# Tikkenteller.net
KiCad netlist of a schematic drawn in EAGLE
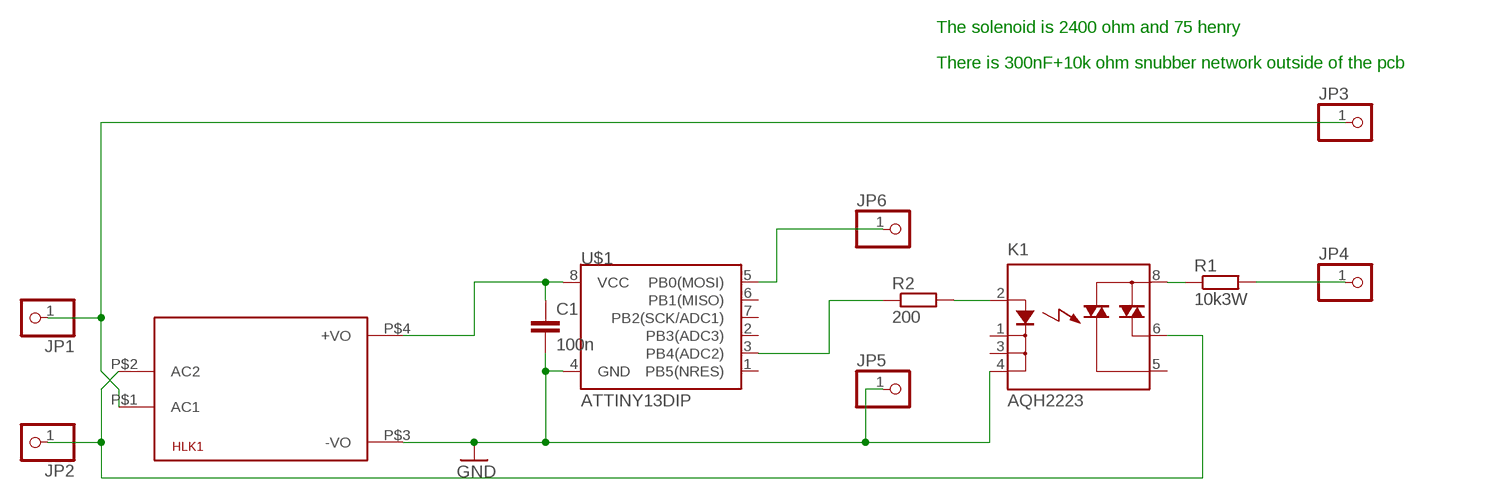
[diagram p0: schematic, sheet 1]

(export (version "E")
  (design (tool "Eeschema 10.0.6"))
  (components
    (comp (ref "C1")
      (value "100n")
      (footprint "eagle-import:C050-024X044")
      (libsource (lib "eagle-import") (part "C-EU050-024X044"))
    )
    (comp (ref "HLK1")
      (value "HLK-PM013W")
      (footprint "eagle-import:HLK-PM01")
      (libsource (lib "eagle-import") (part "HLK-PM013W"))
    )
    (comp (ref "JP1")
      (value "PINHD-1X1")
      (footprint "eagle-import:1X01")
      (libsource (lib "eagle-import") (part "PINHD-1X1"))
    )
    (comp (ref "JP2")
      (value "PINHD-1X1")
      (footprint "eagle-import:1X01")
      (libsource (lib "eagle-import") (part "PINHD-1X1"))
    )
    (comp (ref "JP3")
      (value "PINHD-1X1")
      (footprint "eagle-import:1X01")
      (libsource (lib "eagle-import") (part "PINHD-1X1"))
    )
    (comp (ref "JP4")
      (value "PINHD-1X1")
      (footprint "eagle-import:1X01")
      (libsource (lib "eagle-import") (part "PINHD-1X1"))
    )
    (comp (ref "JP5")
      (value "PINHD-1X1")
      (footprint "eagle-import:1X01")
      (libsource (lib "eagle-import") (part "PINHD-1X1"))
    )
    (comp (ref "JP6")
      (value "PINHD-1X1")
      (footprint "eagle-import:1X01")
      (libsource (lib "eagle-import") (part "PINHD-1X1"))
    )
    (comp (ref "K1")
      (value "AQH2223")
      (footprint "eagle-import:DIL07")
      (fields (field (name "MF") "AROMAT/ MATSUSHITA"))
      (libsource (lib "eagle-import") (part "AQH2232"))
    )
    (comp (ref "R1")
      (value "10k3W")
      (footprint "eagle-import:RESISTOR10")
      (libsource (lib "eagle-import") (part "RR10"))
    )
    (comp (ref "R2")
      (value "200")
      (footprint "eagle-import:RESISTOR4")
      (libsource (lib "eagle-import") (part "RR4"))
    )
    (comp (ref "U$1")
      (value "ATTINY13DIP")
      (footprint "eagle-import:DIP08")
      (libsource (lib "eagle-import") (part "ATTINY13DIP"))
    )
  )
  (nets
    (net (code "1") (name "GND") (class "Default")
      (node (ref "C1") (pin "2") (pinfunction "2_2") (pintype "passive"))
      (node (ref "HLK1") (pin "P$3") (pinfunction "-VO_P$3") (pintype "bidirectional"))
      (node (ref "JP5") (pin "1") (pinfunction "1_1") (pintype "passive"))
      (node (ref "K1") (pin "4") (pinfunction "K2_4") (pintype "passive"))
      (node (ref "U$1") (pin "4") (pinfunction "GND_4") (pintype "bidirectional"))
    )
    (net (code "2") (name "Net-(HLK1-+VO)") (class "Default")
      (node (ref "C1") (pin "1") (pinfunction "1_1") (pintype "passive"))
      (node (ref "HLK1") (pin "P$4") (pinfunction "+VO_P$4") (pintype "bidirectional"))
      (node (ref "U$1") (pin "8") (pinfunction "VCC_8") (pintype "bidirectional"))
    )
    (net (code "3") (name "Net-(HLK1-AC1)") (class "Default")
      (node (ref "HLK1") (pin "P$1") (pinfunction "AC1_P$1") (pintype "bidirectional"))
      (node (ref "JP1") (pin "1") (pinfunction "1_1") (pintype "passive"))
      (node (ref "JP3") (pin "1") (pinfunction "1_1") (pintype "passive"))
    )
    (net (code "4") (name "Net-(HLK1-AC2)") (class "Default")
      (node (ref "HLK1") (pin "P$2") (pinfunction "AC2_P$2") (pintype "bidirectional"))
      (node (ref "JP2") (pin "1") (pinfunction "1_1") (pintype "passive"))
      (node (ref "K1") (pin "6") (pinfunction "DS3_6") (pintype "passive"))
    )
    (net (code "5") (name "Net-(JP4-Pad1)") (class "Default")
      (node (ref "JP4") (pin "1") (pinfunction "1_1") (pintype "passive"))
      (node (ref "R1") (pin "2") (pinfunction "2_2") (pintype "passive"))
    )
    (net (code "6") (name "Net-(K1-A)") (class "Default")
      (node (ref "K1") (pin "2") (pinfunction "A_2") (pintype "passive"))
      (node (ref "R2") (pin "2") (pinfunction "2_2") (pintype "passive"))
    )
    (net (code "7") (name "Net-(K1-DS1)") (class "Default")
      (node (ref "K1") (pin "8") (pinfunction "DS1_8") (pintype "passive"))
      (node (ref "R1") (pin "1") (pinfunction "1_1") (pintype "passive"))
    )
    (net (code "8") (name "Net-(U$1-PB0(MOSI))") (class "Default")
      (node (ref "JP6") (pin "1") (pinfunction "1_1") (pintype "passive"))
      (node (ref "U$1") (pin "5") (pinfunction "PB0(MOSI)_5") (pintype "bidirectional"))
    )
    (net (code "9") (name "Net-(U$1-PB4(ADC2))") (class "Default")
      (node (ref "R2") (pin "1") (pinfunction "1_1") (pintype "passive"))
      (node (ref "U$1") (pin "3") (pinfunction "PB4(ADC2)_3") (pintype "bidirectional"))
    )
    (net (code "10") (name "unconnected-(K1-DS2-Pad5)") (class "Default")
      (node (ref "K1") (pin "5") (pinfunction "DS2_5") (pintype "passive"))
    )
    (net (code "11") (name "unconnected-(K1-K-Pad1)") (class "Default")
      (node (ref "K1") (pin "1") (pinfunction "K_1") (pintype "passive"))
    )
    (net (code "12") (name "unconnected-(K1-K1-Pad3)") (class "Default")
      (node (ref "K1") (pin "3") (pinfunction "K1_3") (pintype "passive"))
    )
    (net (code "13") (name "unconnected-(U$1-PB1(MISO)-Pad6)") (class "Default")
      (node (ref "U$1") (pin "6") (pinfunction "PB1(MISO)_6") (pintype "bidirectional"))
    )
    (net (code "14") (name "unconnected-(U$1-PB2(SCK{slash}ADC1)-Pad7)") (class "Default")
      (node (ref "U$1") (pin "7") (pinfunction "PB2(SCK/ADC1)_7") (pintype "bidirectional"))
    )
    (net (code "15") (name "unconnected-(U$1-PB3(ADC3)-Pad2)") (class "Default")
      (node (ref "U$1") (pin "2") (pinfunction "PB3(ADC3)_2") (pintype "bidirectional"))
    )
    (net (code "16") (name "unconnected-(U$1-PB5(NRES)-Pad1)") (class "Default")
      (node (ref "U$1") (pin "1") (pinfunction "PB5(NRES)_1") (pintype "bidirectional"))
    )
  )
)
